# EVB-A32M1-F_Schematic.net
KiCad netlist of a schematic drawn in Altium Designer
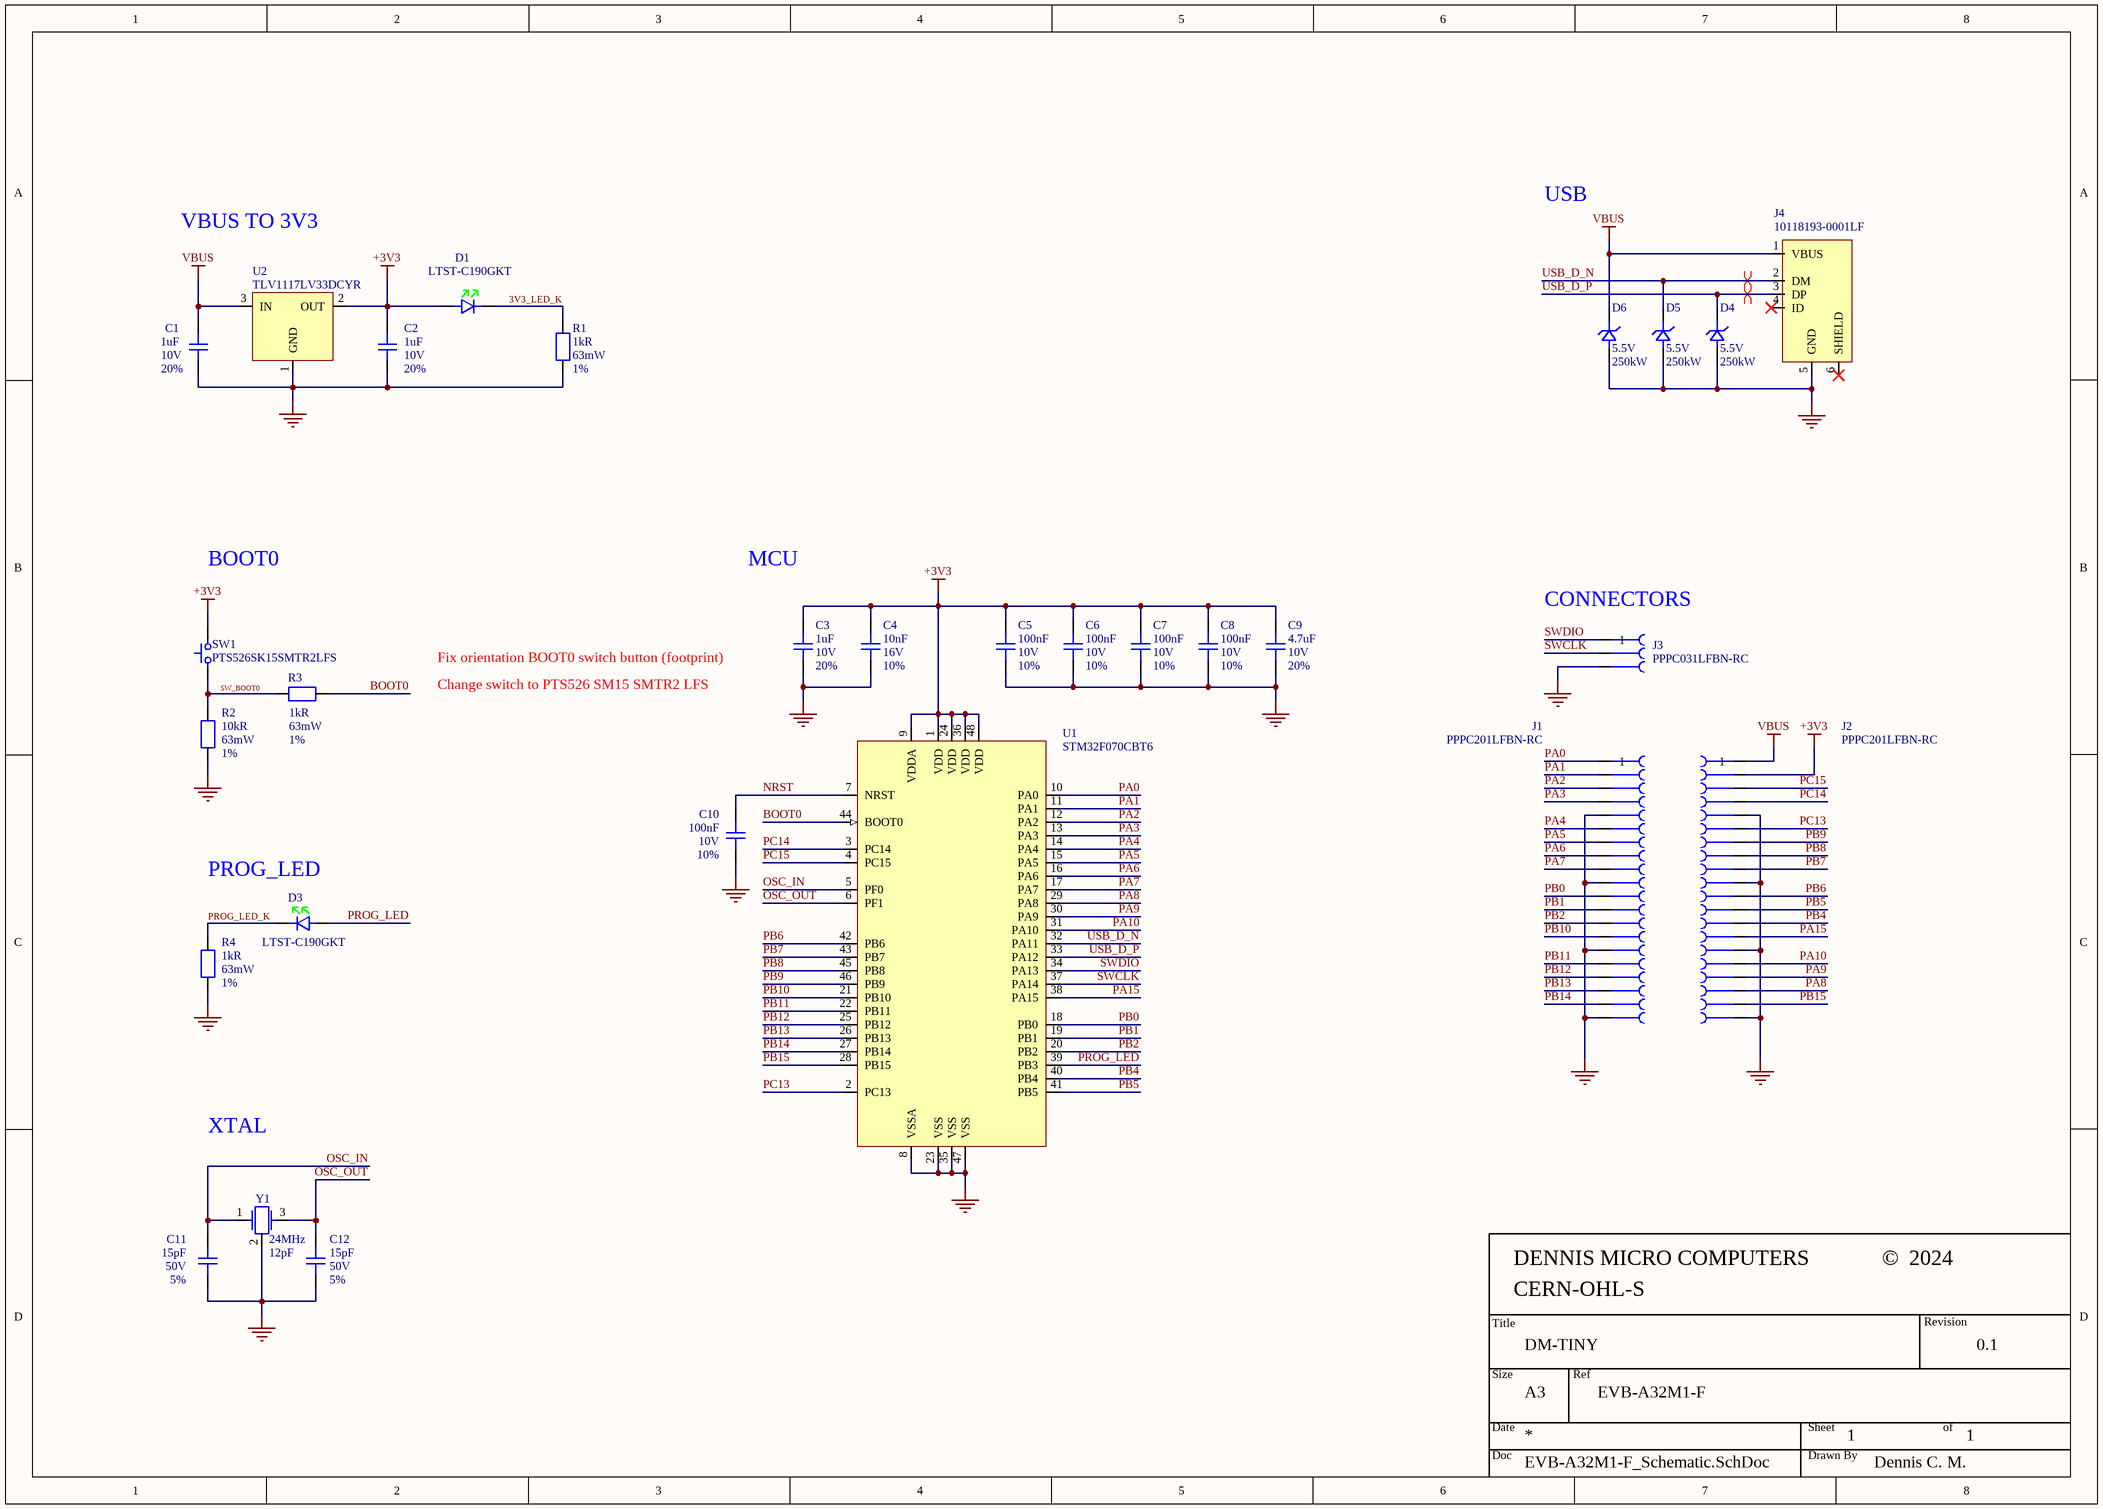
[diagram p0: EVB-A32M1-F_Schematic.SchDoc]

(export (version "E")
  (design (tool "Eeschema 10.0.6"))
  (components
    (comp (ref "C1")
      (value "1uF")
      (footprint "C_Yageo_CC_0402_A")
      (description "Multilayer Ceramic Capacitor, 1 uF, 50 V, ± 10%, X5R, 0402 [1005 Metric]")
      (fields
        (field (name "VOLTAGE RATING (DC)") "10V")
        (field (name "TOLERANCE") "20%")
        (field (name "LCSC PART NUMBER") "C113791")
        (field (name "Comment") "CC0402MRX5R6BB105")
      )
      (libsource (lib "Dennis Micro Computers") (part "C"))
    )
    (comp (ref "C2")
      (value "1uF")
      (footprint "C_Yageo_CC_0402_A")
      (description "Multilayer Ceramic Capacitor, 1 uF, 50 V, ± 10%, X5R, 0402 [1005 Metric]")
      (fields
        (field (name "VOLTAGE RATING (DC)") "10V")
        (field (name "TOLERANCE") "20%")
        (field (name "LCSC PART NUMBER") "C113791")
        (field (name "Comment") "CC0402MRX5R6BB105")
      )
      (libsource (lib "Dennis Micro Computers") (part "C"))
    )
    (comp (ref "C3")
      (value "1uF")
      (footprint "C_Yageo_CC_0402_A")
      (description "Multilayer Ceramic Capacitor, 1 uF, 50 V, ± 10%, X5R, 0402 [1005 Metric]")
      (fields
        (field (name "VOLTAGE RATING (DC)") "10V")
        (field (name "TOLERANCE") "20%")
        (field (name "LCSC PART NUMBER") "C113791")
        (field (name "Comment") "CC0402MRX5R6BB105")
      )
      (libsource (lib "Dennis Micro Computers") (part "C"))
    )
    (comp (ref "C4")
      (value "10nF")
      (footprint "C_Yageo_CC_0402_A")
      (description "Multilayer Ceramic Capacitor, 0.01 uF, 16 V, ± 10%, X7R, 0402 [1005 Metric]")
      (fields
        (field (name "TOLERANCE") "10%")
        (field (name "VOLTAGE RATING") "16V")
        (field (name "Comment") "CC0402KRX7R7BB103")
      )
      (libsource (lib "Dennis Micro Computers") (part "C"))
    )
    (comp (ref "C5")
      (value "100nF")
      (footprint "C_Samsung_CL_0402_A")
      (description "Multilayer Ceramic Capacitor, 0.1 uF, 10 V, ± 10%, X7R, 0402 [1005 Metric]")
      (fields
        (field (name "VOLTAGE RATING (DC)") "10V")
        (field (name "TOLERANCE") "10%")
        (field (name "Comment") "CL05B104KP5NNNC")
      )
      (libsource (lib "Dennis Micro Computers") (part "C"))
    )
    (comp (ref "C6")
      (value "100nF")
      (footprint "C_Samsung_CL_0402_A")
      (description "Multilayer Ceramic Capacitor, 0.1 uF, 10 V, ± 10%, X7R, 0402 [1005 Metric]")
      (fields
        (field (name "VOLTAGE RATING (DC)") "10V")
        (field (name "TOLERANCE") "10%")
        (field (name "Comment") "CL05B104KP5NNNC")
      )
      (libsource (lib "Dennis Micro Computers") (part "C"))
    )
    (comp (ref "C7")
      (value "100nF")
      (footprint "C_Samsung_CL_0402_A")
      (description "Multilayer Ceramic Capacitor, 0.1 uF, 10 V, ± 10%, X7R, 0402 [1005 Metric]")
      (fields
        (field (name "VOLTAGE RATING") "10V")
        (field (name "TOLERANCE") "10%")
        (field (name "Comment") "CL05B104KP5NNNC")
      )
      (libsource (lib "Dennis Micro Computers") (part "C"))
    )
    (comp (ref "C8")
      (value "100nF")
      (footprint "C_Samsung_CL_0402_A")
      (description "Multilayer Ceramic Capacitor, 0.1 uF, 10 V, ± 10%, X7R, 0402 [1005 Metric]")
      (fields
        (field (name "VOLTAGE RATING") "10V")
        (field (name "TOLERANCE") "10%")
        (field (name "Comment") "CL05B104KP5NNNC")
      )
      (libsource (lib "Dennis Micro Computers") (part "C"))
    )
    (comp (ref "C9")
      (value "4.7uF")
      (footprint "C_Samsung_CL_0402_A")
      (description "Multilayer Ceramic Capacitor, 4.7 uF, 10 V, ± 20%, X5R, 0402 [1005 Metric]")
      (fields
        (field (name "TOLERANCE") "20%")
        (field (name "VOLTAGE RATING") "10V")
        (field (name "Comment") "CL05A475MP5NRNC")
      )
      (libsource (lib "Dennis Micro Computers") (part "C"))
    )
    (comp (ref "C10")
      (value "100nF")
      (footprint "C_Samsung_CL_0402_A")
      (description "Multilayer Ceramic Capacitor, 0.1 uF, 10 V, ± 10%, X7R, 0402 [1005 Metric]")
      (fields
        (field (name "VOLTAGE RATING (DC)") "10V")
        (field (name "TOLERANCE") "10%")
        (field (name "Comment") "CL05B104KP5NNNC")
      )
      (libsource (lib "Dennis Micro Computers") (part "C"))
    )
    (comp (ref "C11")
      (value "15pF")
      (footprint "C_Yageo_CC_0402_A")
      (description "Multilayer Ceramic Capacitor, 15 pF, 10 V, ± 5%, X7R, 0402 [1005 Metric]")
      (fields
        (field (name "TOLERANCE") "5%")
        (field (name "VOLTAGE RATING") "50V")
        (field (name "VOLTAGE") "50V")
        (field (name "Comment") "CC0402JRNPO9BN150")
      )
      (libsource (lib "Dennis Micro Computers") (part "C"))
    )
    (comp (ref "C12")
      (value "15pF")
      (footprint "C_Yageo_CC_0402_A")
      (description "Multilayer Ceramic Capacitor, 15 pF, 10 V, ± 5%, X7R, 0402 [1005 Metric]")
      (fields
        (field (name "TOLERANCE") "5%")
        (field (name "VOLTAGE RATING") "50V")
        (field (name "VOLTAGE") "50V")
        (field (name "Comment") "CC0402JRNPO9BN150")
      )
      (libsource (lib "Dennis Micro Computers") (part "C"))
    )
    (comp (ref "D1")
      (value "LTST-C190GKT")
      (footprint "D_LED_Lite-On_Green_0603_A")
      (description "LED Uni-Color Green 565nm 2-Pin Chip LED T/R")
      (fields (field (name "VOLTAGE") "2V"))
      (libsource (lib "Dennis Micro Computers") (part "D_LED_Green"))
    )
    (comp (ref "D3")
      (value "LTST-C190GKT")
      (footprint "D_LED_Lite-On_Green_0603_A")
      (description "LED Uni-Color Green 565nm 2-Pin Chip LED T/R")
      (fields (field (name "VOLTAGE") "2V"))
      (libsource (lib "Dennis Micro Computers") (part "D_LED_Green"))
    )
    (comp (ref "D4")
      (value "D5V0F1U2S9-7")
      (footprint "D_TVS_Uni_Diodes_SOD-923_B")
      (description "Diode TVS Dual Uni-Dir 5.5V 250000W 2-Pin SOD-923 T/R")
      (fields (field (name "REVERSE STANDOFF VOLTAGE") "5.5V") (field (name "PEAK PULSE POWER") "250kW"))
      (libsource (lib "Dennis Micro Computers") (part "D_TVS_Uni"))
    )
    (comp (ref "D5")
      (value "D5V0F1U2S9-7")
      (footprint "D_TVS_Uni_Diodes_SOD-923_B")
      (description "Diode TVS Dual Uni-Dir 5.5V 250000W 2-Pin SOD-923 T/R")
      (fields (field (name "REVERSE STANDOFF VOLTAGE") "5.5V") (field (name "PEAK PULSE POWER") "250kW"))
      (libsource (lib "Dennis Micro Computers") (part "D_TVS_Uni"))
    )
    (comp (ref "D6")
      (value "D5V0F1U2S9-7")
      (footprint "D_TVS_Uni_Diodes_SOD-923_B")
      (description "Diode TVS Dual Uni-Dir 5.5V 250000W 2-Pin SOD-923 T/R")
      (fields (field (name "REVERSE STANDOFF VOLTAGE") "5.5V") (field (name "PEAK PULSE POWER") "250kW"))
      (libsource (lib "Dennis Micro Computers") (part "D_TVS_Uni"))
    )
    (comp (ref "J1")
      (value "PPPC201LFBN-RC")
      (footprint "J_Cast_TH20_Top_2.54mm")
      (description "20 Position Total Single Row 2.54 mm Pitch Straight Female Header")
      (libsource (lib "") (part "J_01x20_Socket_1"))
    )
    (comp (ref "J2")
      (value "PPPC201LFBN-RC")
      (footprint "J_Cast_TH20_Bottom_2.54mm")
      (description "20 Position Total Single Row 2.54 mm Pitch Straight Female Header")
      (libsource (lib "Dennis Micro Computers") (part "J_01x20_Socket"))
    )
    (comp (ref "J3")
      (value "PPPC031LFBN-RC")
      (footprint "J_Cast_TH3_Bottom_2.54mm")
      (description "3 Position Total Single Row 2.54 mm Pitch Straight Female Header")
      (libsource (lib "Dennis Micro Computers") (part "J_01x03_Socket"))
    )
    (comp (ref "J4")
      (value "10118193-0001LF")
      (footprint "J_USB_Micro-B_Amphenol_10118193-0001LF")
      (description "Usb Connector, 5 Contact(S), Female, Right Angle, Surface Mount Terminal, Locking, Receptacle")
      (libsource (lib "Dennis Micro Computers") (part "J_USB2_B_Micro"))
    )
    (comp (ref "R1")
      (value "1kR")
      (footprint "R_Yageo_RCL_0402_A")
      (description "SMD Chip Resistor, 1 kOhm, ± 1%, 62.5 mW, 0402 [1005 Metric], Thick Film, General Purpose")
      (fields
        (field (name "MAX POWER DISSIPATION") "63mW")
        (field (name "RESISTANCE TOLERANCE") "1%")
        (field (name "TOLERANCE") "1%")
        (field (name "Comment") "RC0402FR-071KL")
      )
      (libsource (lib "Dennis Micro Computers") (part "R"))
    )
    (comp (ref "R2")
      (value "10kR")
      (footprint "R_Yageo_RCL_0402_A")
      (description "SMD Chip Resistor, 10 kOhm, ± 1%, 62.5 mW, 0402 [1005 Metric], Thick Film, General Purpose")
      (fields
        (field (name "RESISTANCE TOLERANCE") "1%")
        (field (name "TOLERANCE") "1%")
        (field (name "MAX POWER DISSIPATION") "63mW")
        (field (name "Comment") "RC0402FR-0710KL")
      )
      (libsource (lib "Dennis Micro Computers") (part "R"))
    )
    (comp (ref "R3")
      (value "1kR")
      (footprint "R_Yageo_RCL_0402_A")
      (description "SMD Chip Resistor, 1 kOhm, ± 1%, 62.5 mW, 0402 [1005 Metric], Thick Film, General Purpose")
      (fields
        (field (name "MAX POWER DISSIPATION") "63mW")
        (field (name "RESISTANCE TOLERANCE") "1%")
        (field (name "TOLERANCE") "1%")
        (field (name "Comment") "RC0402FR-071KL")
      )
      (libsource (lib "Dennis Micro Computers") (part "R"))
    )
    (comp (ref "R4")
      (value "1kR")
      (footprint "R_Yageo_RCL_0402_A")
      (description "SMD Chip Resistor, 1 kOhm, ± 1%, 62.5 mW, 0402 [1005 Metric], Thick Film, General Purpose")
      (fields
        (field (name "MAX POWER DISSIPATION") "63mW")
        (field (name "RESISTANCE TOLERANCE") "1%")
        (field (name "TOLERANCE") "1%")
        (field (name "Comment") "RC0402FR-071KL")
      )
      (libsource (lib "Dennis Micro Computers") (part "R"))
    )
    (comp (ref "SW1")
      (value "PTS526SK15SMTR2LFS")
      (footprint "SW_Tactitle_SPST_C&K_PTS526 SK15 SMTR2 LFS")
      (description "Switch Tactile N.O. SPST Round Button Gull Wing 0.05A 12VDC 200000Cycles 2.45N SMD T/R")
      (libsource (lib "Dennis Micro Computers") (part "SW_Tactile_SPST"))
    )
    (comp (ref "U1")
      (value "STM32F070CBT6")
      (footprint "U_ST_LQFP48_B")
      (description "IC MCU 32BIT 128KB FLASH 48LQFP")
      (libsource (lib "Dennis Micro Computers") (part "U_STM32F070CB"))
    )
    (comp (ref "U2")
      (value "TLV1117LV33DCYR")
      (footprint "U_TI_SOT-223_B")
      (description "LDO Regulator Pos 3.3V 1A 4-Pin(3+Tab) SOT-223 T/R")
      (libsource (lib "Dennis Micro Computers") (part "U_TLV1117LV"))
    )
    (comp (ref "Y1")
      (value "ECS-240-12-37B-CKY-TR")
      (footprint "Y_Crystal_GND24_ECS_240-12-37B-CKY-TR")
      (description "Crystal 24MHz ±10ppm (Tol) ±10ppm (Stability) 12pF FUND 50Ohm 4-Pin Mini-CSMD T/R")
      (fields (field (name "FREQUENCY") "24MHz") (field (name "LOAD CAPACITANCE") "12pF"))
      (libsource (lib "Dennis Micro Computers") (part "Y_Crystal_GND24"))
    )
  )
  (nets
    (net (code "1") (name "+3V3") (class "Default")
      (node (ref "C2") (pin "2") (pinfunction "2_2") (pintype "passive"))
      (node (ref "C3") (pin "2") (pinfunction "2_2") (pintype "passive"))
      (node (ref "C4") (pin "2") (pinfunction "2_2") (pintype "passive"))
      (node (ref "C5") (pin "2") (pinfunction "2_2") (pintype "passive"))
      (node (ref "C6") (pin "2") (pinfunction "2_2") (pintype "passive"))
      (node (ref "C7") (pin "2") (pinfunction "2_2") (pintype "passive"))
      (node (ref "C8") (pin "2") (pinfunction "2_2") (pintype "passive"))
      (node (ref "C9") (pin "2") (pinfunction "2_2") (pintype "passive"))
      (node (ref "D1") (pin "2") (pinfunction "2_2") (pintype "passive"))
      (node (ref "J2") (pin "2") (pinfunction "2_2") (pintype "passive"))
      (node (ref "SW1") (pin "2") (pinfunction "2_2") (pintype "passive"))
      (node (ref "U1") (pin "1") (pinfunction "VDD_1") (pintype "power_in"))
      (node (ref "U1") (pin "24") (pinfunction "VDD_24") (pintype "power_in"))
      (node (ref "U1") (pin "36") (pinfunction "VDD_36") (pintype "power_in"))
      (node (ref "U1") (pin "48") (pinfunction "VDD_48") (pintype "power_in"))
      (node (ref "U1") (pin "9") (pinfunction "VDDA_9") (pintype "power_in"))
      (node (ref "U2") (pin "2") (pinfunction "OUT_2") (pintype "power_in"))
    )
    (net (code "2") (name "/3V3_LED_K") (class "Default")
      (node (ref "D1") (pin "1") (pinfunction "1_1") (pintype "passive"))
      (node (ref "R1") (pin "2") (pinfunction "2_2") (pintype "passive"))
    )
    (net (code "3") (name "/BOOT0") (class "Default")
      (node (ref "R3") (pin "1") (pinfunction "1_1") (pintype "passive"))
      (node (ref "U1") (pin "44") (pinfunction "BOOT0_44") (pintype "input"))
    )
    (net (code "4") (name "/NRST") (class "Default")
      (node (ref "C10") (pin "2") (pinfunction "2_2") (pintype "passive"))
      (node (ref "U1") (pin "7") (pinfunction "NRST_7") (pintype "bidirectional"))
    )
    (net (code "5") (name "/OSC_IN") (class "Default")
      (node (ref "C11") (pin "2") (pinfunction "2_2") (pintype "passive"))
      (node (ref "U1") (pin "5") (pinfunction "PF0_5") (pintype "bidirectional"))
      (node (ref "Y1") (pin "1") (pinfunction "1_1") (pintype "passive"))
    )
    (net (code "6") (name "/OSC_OUT") (class "Default")
      (node (ref "C12") (pin "2") (pinfunction "2_2") (pintype "passive"))
      (node (ref "U1") (pin "6") (pinfunction "PF1_6") (pintype "bidirectional"))
      (node (ref "Y1") (pin "3") (pinfunction "3_3") (pintype "passive"))
    )
    (net (code "7") (name "/PA0") (class "Default")
      (node (ref "J1") (pin "1") (pinfunction "1_1") (pintype "passive"))
      (node (ref "U1") (pin "10") (pinfunction "PA0_10") (pintype "bidirectional"))
    )
    (net (code "8") (name "/PA1") (class "Default")
      (node (ref "J1") (pin "2") (pinfunction "2_2") (pintype "passive"))
      (node (ref "U1") (pin "11") (pinfunction "PA1_11") (pintype "bidirectional"))
    )
    (net (code "9") (name "/PA2") (class "Default")
      (node (ref "J1") (pin "3") (pinfunction "3_3") (pintype "passive"))
      (node (ref "U1") (pin "12") (pinfunction "PA2_12") (pintype "bidirectional"))
    )
    (net (code "10") (name "/PA3") (class "Default")
      (node (ref "J1") (pin "4") (pinfunction "4_4") (pintype "passive"))
      (node (ref "U1") (pin "13") (pinfunction "PA3_13") (pintype "bidirectional"))
    )
    (net (code "11") (name "/PA4") (class "Default")
      (node (ref "J1") (pin "6") (pinfunction "6_6") (pintype "passive"))
      (node (ref "U1") (pin "14") (pinfunction "PA4_14") (pintype "bidirectional"))
    )
    (net (code "12") (name "/PA5") (class "Default")
      (node (ref "J1") (pin "7") (pinfunction "7_7") (pintype "passive"))
      (node (ref "U1") (pin "15") (pinfunction "PA5_15") (pintype "bidirectional"))
    )
    (net (code "13") (name "/PA6") (class "Default")
      (node (ref "J1") (pin "8") (pinfunction "8_8") (pintype "passive"))
      (node (ref "U1") (pin "16") (pinfunction "PA6_16") (pintype "bidirectional"))
    )
    (net (code "14") (name "/PA7") (class "Default")
      (node (ref "J1") (pin "9") (pinfunction "9_9") (pintype "passive"))
      (node (ref "U1") (pin "17") (pinfunction "PA7_17") (pintype "bidirectional"))
    )
    (net (code "15") (name "/PA8") (class "Default")
      (node (ref "J2") (pin "18") (pinfunction "18_18") (pintype "passive"))
      (node (ref "U1") (pin "29") (pinfunction "PA8_29") (pintype "bidirectional"))
    )
    (net (code "16") (name "/PA9") (class "Default")
      (node (ref "J2") (pin "17") (pinfunction "17_17") (pintype "passive"))
      (node (ref "U1") (pin "30") (pinfunction "PA9_30") (pintype "bidirectional"))
    )
    (net (code "17") (name "/PA10") (class "Default")
      (node (ref "J2") (pin "16") (pinfunction "16_16") (pintype "passive"))
      (node (ref "U1") (pin "31") (pinfunction "PA10_31") (pintype "bidirectional"))
    )
    (net (code "18") (name "/PA15") (class "Default")
      (node (ref "J2") (pin "14") (pinfunction "14_14") (pintype "passive"))
      (node (ref "U1") (pin "38") (pinfunction "PA15_38") (pintype "bidirectional"))
    )
    (net (code "19") (name "/PB0") (class "Default")
      (node (ref "J1") (pin "11") (pinfunction "11_11") (pintype "passive"))
      (node (ref "U1") (pin "18") (pinfunction "PB0_18") (pintype "bidirectional"))
    )
    (net (code "20") (name "/PB1") (class "Default")
      (node (ref "J1") (pin "12") (pinfunction "12_12") (pintype "passive"))
      (node (ref "U1") (pin "19") (pinfunction "PB1_19") (pintype "bidirectional"))
    )
    (net (code "21") (name "/PB2") (class "Default")
      (node (ref "J1") (pin "13") (pinfunction "13_13") (pintype "passive"))
      (node (ref "U1") (pin "20") (pinfunction "PB2_20") (pintype "bidirectional"))
    )
    (net (code "22") (name "/PB4") (class "Default")
      (node (ref "J2") (pin "13") (pinfunction "13_13") (pintype "passive"))
      (node (ref "U1") (pin "40") (pinfunction "PB4_40") (pintype "bidirectional"))
    )
    (net (code "23") (name "/PB5") (class "Default")
      (node (ref "J2") (pin "12") (pinfunction "12_12") (pintype "passive"))
      (node (ref "U1") (pin "41") (pinfunction "PB5_41") (pintype "bidirectional"))
    )
    (net (code "24") (name "/PB6") (class "Default")
      (node (ref "J2") (pin "11") (pinfunction "11_11") (pintype "passive"))
      (node (ref "U1") (pin "42") (pinfunction "PB6_42") (pintype "bidirectional"))
    )
    (net (code "25") (name "/PB7") (class "Default")
      (node (ref "J2") (pin "9") (pinfunction "9_9") (pintype "passive"))
      (node (ref "U1") (pin "43") (pinfunction "PB7_43") (pintype "bidirectional"))
    )
    (net (code "26") (name "/PB8") (class "Default")
      (node (ref "J2") (pin "8") (pinfunction "8_8") (pintype "passive"))
      (node (ref "U1") (pin "45") (pinfunction "PB8_45") (pintype "bidirectional"))
    )
    (net (code "27") (name "/PB9") (class "Default")
      (node (ref "J2") (pin "7") (pinfunction "7_7") (pintype "passive"))
      (node (ref "U1") (pin "46") (pinfunction "PB9_46") (pintype "bidirectional"))
    )
    (net (code "28") (name "/PB10") (class "Default")
      (node (ref "J1") (pin "14") (pinfunction "14_14") (pintype "passive"))
      (node (ref "U1") (pin "21") (pinfunction "PB10_21") (pintype "bidirectional"))
    )
    (net (code "29") (name "/PB11") (class "Default")
      (node (ref "J1") (pin "16") (pinfunction "16_16") (pintype "passive"))
      (node (ref "U1") (pin "22") (pinfunction "PB11_22") (pintype "bidirectional"))
    )
    (net (code "30") (name "/PB12") (class "Default")
      (node (ref "J1") (pin "17") (pinfunction "17_17") (pintype "passive"))
      (node (ref "U1") (pin "25") (pinfunction "PB12_25") (pintype "bidirectional"))
    )
    (net (code "31") (name "/PB13") (class "Default")
      (node (ref "J1") (pin "18") (pinfunction "18_18") (pintype "passive"))
      (node (ref "U1") (pin "26") (pinfunction "PB13_26") (pintype "bidirectional"))
    )
    (net (code "32") (name "/PB14") (class "Default")
      (node (ref "J1") (pin "19") (pinfunction "19_19") (pintype "passive"))
      (node (ref "U1") (pin "27") (pinfunction "PB14_27") (pintype "bidirectional"))
    )
    (net (code "33") (name "/PB15") (class "Default")
      (node (ref "J2") (pin "19") (pinfunction "19_19") (pintype "passive"))
      (node (ref "U1") (pin "28") (pinfunction "PB15_28") (pintype "bidirectional"))
    )
    (net (code "34") (name "/PC13") (class "Default")
      (node (ref "J2") (pin "6") (pinfunction "6_6") (pintype "passive"))
      (node (ref "U1") (pin "2") (pinfunction "PC13_2") (pintype "bidirectional"))
    )
    (net (code "35") (name "/PC14") (class "Default")
      (node (ref "J2") (pin "4") (pinfunction "4_4") (pintype "passive"))
      (node (ref "U1") (pin "3") (pinfunction "PC14_3") (pintype "bidirectional"))
    )
    (net (code "36") (name "/PC15") (class "Default")
      (node (ref "J2") (pin "3") (pinfunction "3_3") (pintype "passive"))
      (node (ref "U1") (pin "4") (pinfunction "PC15_4") (pintype "bidirectional"))
    )
    (net (code "37") (name "/PROG_LED") (class "Default")
      (node (ref "D3") (pin "2") (pinfunction "2_2") (pintype "passive"))
      (node (ref "U1") (pin "39") (pinfunction "PB3_39") (pintype "bidirectional"))
    )
    (net (code "38") (name "/PROG_LED_K") (class "Default")
      (node (ref "D3") (pin "1") (pinfunction "1_1") (pintype "passive"))
      (node (ref "R4") (pin "2") (pinfunction "2_2") (pintype "passive"))
    )
    (net (code "39") (name "/SWCLK") (class "Default")
      (node (ref "J3") (pin "2") (pinfunction "2_2") (pintype "passive"))
      (node (ref "U1") (pin "37") (pinfunction "PA14_37") (pintype "bidirectional"))
    )
    (net (code "40") (name "/SWDIO") (class "Default")
      (node (ref "J3") (pin "1") (pinfunction "1_1") (pintype "passive"))
      (node (ref "U1") (pin "34") (pinfunction "PA13_34") (pintype "bidirectional"))
    )
    (net (code "41") (name "/SW_BOOT0") (class "Default")
      (node (ref "R2") (pin "2") (pinfunction "2_2") (pintype "passive"))
      (node (ref "R3") (pin "2") (pinfunction "2_2") (pintype "passive"))
      (node (ref "SW1") (pin "1") (pinfunction "1_1") (pintype "passive"))
    )
    (net (code "42") (name "/USB_D_N") (class "Default")
      (node (ref "D5") (pin "1") (pinfunction "1_1") (pintype "passive"))
      (node (ref "J4") (pin "2") (pinfunction "DM_2") (pintype "bidirectional"))
      (node (ref "U1") (pin "32") (pinfunction "PA11_32") (pintype "bidirectional"))
    )
    (net (code "43") (name "/USB_D_P") (class "Default")
      (node (ref "D4") (pin "1") (pinfunction "1_1") (pintype "passive"))
      (node (ref "J4") (pin "3") (pinfunction "DP_3") (pintype "bidirectional"))
      (node (ref "U1") (pin "33") (pinfunction "PA12_33") (pintype "bidirectional"))
    )
    (net (code "44") (name "GND") (class "Default")
      (node (ref "C1") (pin "1") (pinfunction "1_1") (pintype "passive"))
      (node (ref "C10") (pin "1") (pinfunction "1_1") (pintype "passive"))
      (node (ref "C11") (pin "1") (pinfunction "1_1") (pintype "passive"))
      (node (ref "C12") (pin "1") (pinfunction "1_1") (pintype "passive"))
      (node (ref "C2") (pin "1") (pinfunction "1_1") (pintype "passive"))
      (node (ref "C3") (pin "1") (pinfunction "1_1") (pintype "passive"))
      (node (ref "C4") (pin "1") (pinfunction "1_1") (pintype "passive"))
      (node (ref "C5") (pin "1") (pinfunction "1_1") (pintype "passive"))
      (node (ref "C6") (pin "1") (pinfunction "1_1") (pintype "passive"))
      (node (ref "C7") (pin "1") (pinfunction "1_1") (pintype "passive"))
      (node (ref "C8") (pin "1") (pinfunction "1_1") (pintype "passive"))
      (node (ref "C9") (pin "1") (pinfunction "1_1") (pintype "passive"))
      (node (ref "D4") (pin "2") (pinfunction "2_2") (pintype "passive"))
      (node (ref "D5") (pin "2") (pinfunction "2_2") (pintype "passive"))
      (node (ref "D6") (pin "2") (pinfunction "2_2") (pintype "passive"))
      (node (ref "J1") (pin "10") (pinfunction "10_10") (pintype "passive"))
      (node (ref "J1") (pin "15") (pinfunction "15_15") (pintype "passive"))
      (node (ref "J1") (pin "20") (pinfunction "20_20") (pintype "passive"))
      (node (ref "J1") (pin "5") (pinfunction "5_5") (pintype "passive"))
      (node (ref "J2") (pin "10") (pinfunction "10_10") (pintype "passive"))
      (node (ref "J2") (pin "15") (pinfunction "15_15") (pintype "passive"))
      (node (ref "J2") (pin "20") (pinfunction "20_20") (pintype "passive"))
      (node (ref "J2") (pin "5") (pinfunction "5_5") (pintype "passive"))
      (node (ref "J3") (pin "3") (pinfunction "3_3") (pintype "passive"))
      (node (ref "J4") (pin "5") (pinfunction "GND_5") (pintype "power_in"))
      (node (ref "R1") (pin "1") (pinfunction "1_1") (pintype "passive"))
      (node (ref "R2") (pin "1") (pinfunction "1_1") (pintype "passive"))
      (node (ref "R4") (pin "1") (pinfunction "1_1") (pintype "passive"))
      (node (ref "U1") (pin "23") (pinfunction "VSS_23") (pintype "power_in"))
      (node (ref "U1") (pin "35") (pinfunction "VSS_35") (pintype "power_in"))
      (node (ref "U1") (pin "47") (pinfunction "VSS_47") (pintype "power_in"))
      (node (ref "U1") (pin "8") (pinfunction "VSSA_8") (pintype "power_in"))
      (node (ref "U2") (pin "1") (pinfunction "GND_1") (pintype "power_in"))
      (node (ref "Y1") (pin "2") (pinfunction "2_2") (pintype "passive"))
    )
    (net (code "45") (name "VBUS") (class "Default")
      (node (ref "C1") (pin "2") (pinfunction "2_2") (pintype "passive"))
      (node (ref "D6") (pin "1") (pinfunction "1_1") (pintype "passive"))
      (node (ref "J2") (pin "1") (pinfunction "1_1") (pintype "passive"))
      (node (ref "J4") (pin "1") (pinfunction "VBUS_1") (pintype "power_in"))
      (node (ref "U2") (pin "3") (pinfunction "IN_3") (pintype "power_in"))
    )
    (net (code "46") (name "unconnected-(J4-ID-Pad4)") (class "Default")
      (node (ref "J4") (pin "4") (pinfunction "ID_4") (pintype "passive+no_connect"))
    )
    (net (code "47") (name "unconnected-(J4-SHIELD-Pad6)") (class "Default")
      (node (ref "J4") (pin "6") (pinfunction "SHIELD_6") (pintype "passive+no_connect"))
    )
  )
)
